# Un_C8051F340_V2_0.net
KiCad netlist of a schematic drawn in EAGLE
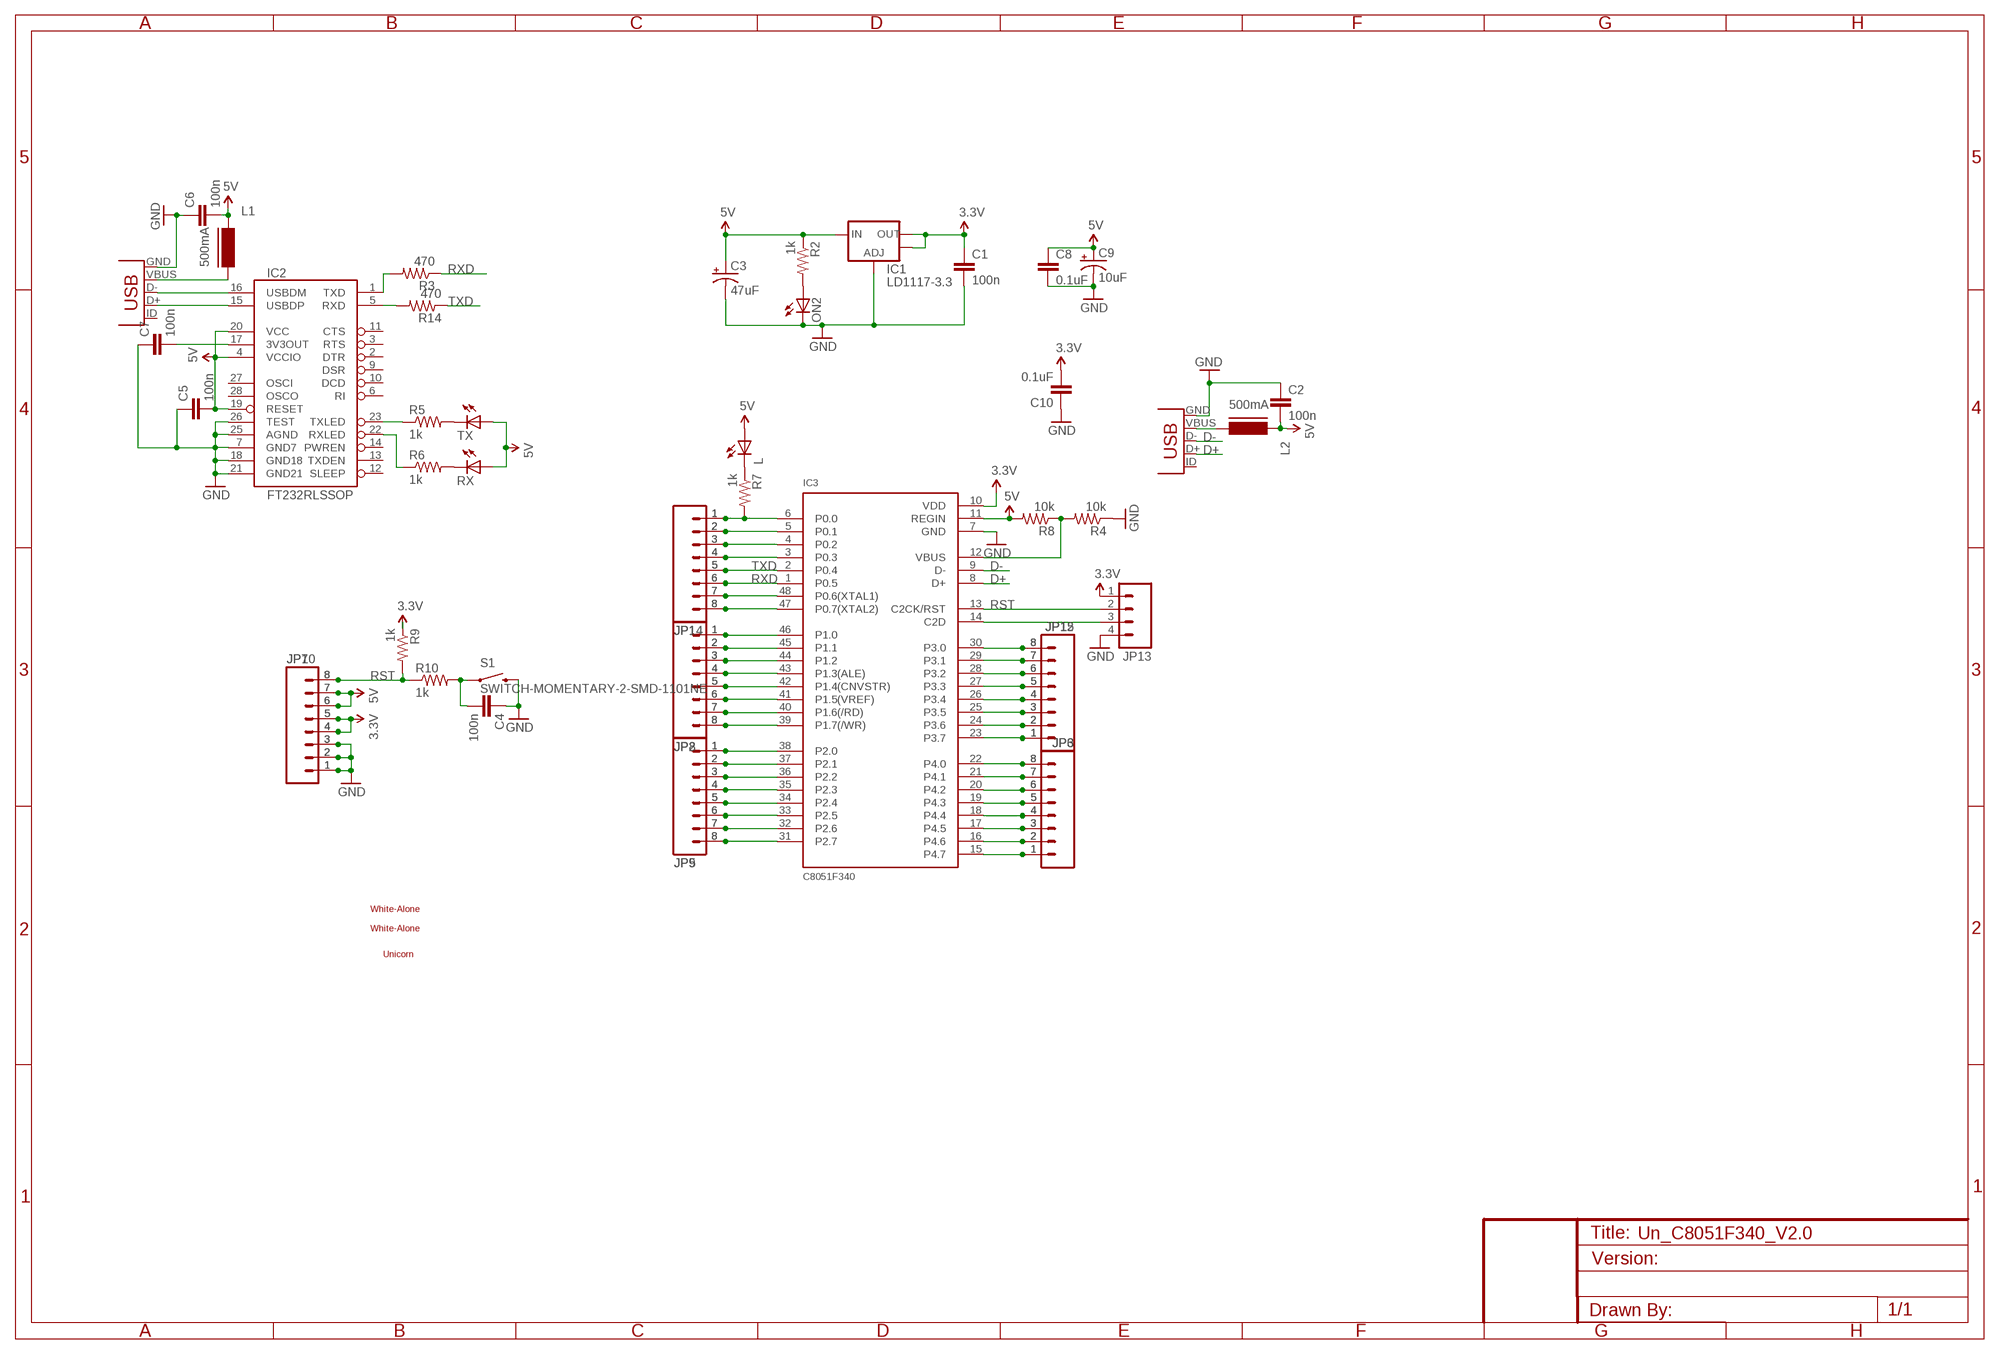
[diagram p0: schematic, sheet 1]

(export (version "E")
  (design (tool "Eeschema 10.0.6"))
  (components
    (comp (ref "C1")
      (value "100n")
      (footprint "eagle-import:0603-CAP")
      (libsource (lib "eagle-import") (part "2SparkFun_CAP0603-CAP"))
    )
    (comp (ref "C2")
      (value "100n")
      (footprint "eagle-import:0603-CAP")
      (libsource (lib "eagle-import") (part "CAP0603-CAP"))
    )
    (comp (ref "C3")
      (value "47uF")
      (footprint "eagle-import:PANASONIC_D")
      (libsource (lib "eagle-import") (part "CAP_POLD"))
    )
    (comp (ref "C4")
      (value "100n")
      (footprint "eagle-import:0603-CAP")
      (libsource (lib "eagle-import") (part "CAP0603-CAP"))
    )
    (comp (ref "C5")
      (value "100n")
      (footprint "eagle-import:0603-CAP")
      (libsource (lib "eagle-import") (part "2SparkFun_CAP0603-CAP"))
    )
    (comp (ref "C6")
      (value "100n")
      (footprint "eagle-import:0603-CAP")
      (libsource (lib "eagle-import") (part "2SparkFun_CAP0603-CAP"))
    )
    (comp (ref "C7")
      (value "100n")
      (footprint "eagle-import:0603-CAP")
      (libsource (lib "eagle-import") (part "2SparkFun_CAP0603-CAP"))
    )
    (comp (ref "C8")
      (value "0.1uF")
      (footprint "eagle-import:0603-CAP")
      (libsource (lib "eagle-import") (part "2SparkFun_CAP0603-CAP"))
    )
    (comp (ref "C9")
      (value "10uF")
      (footprint "eagle-import:EIA3216")
      (libsource (lib "eagle-import") (part "CAP_POL1206"))
    )
    (comp (ref "C10")
      (value "0.1uF")
      (footprint "eagle-import:0603-CAP")
      (libsource (lib "eagle-import") (part "2SparkFun_CAP0603-CAP"))
    )
    (comp (ref "IC1")
      (value "LD1117-3.3")
      (footprint "eagle-import:SOT223")
      (libsource (lib "eagle-import") (part "V_REG_LM1117SOT223"))
    )
    (comp (ref "IC2")
      (value "FT232RLSSOP")
      (footprint "eagle-import:SSOP28DB")
      (libsource (lib "eagle-import") (part "FT232RLSSOP"))
    )
    (comp (ref "IC3")
      (value "C8051F340")
      (footprint "eagle-import:TQFP48")
      (libsource (lib "eagle-import") (part "C8051F340"))
    )
    (comp (ref "JP1")
      (value "M08")
      (footprint "eagle-import:1X08")
      (libsource (lib "eagle-import") (part "M08"))
    )
    (comp (ref "JP2")
      (value "M08")
      (footprint "eagle-import:1X08")
      (libsource (lib "eagle-import") (part "M08"))
    )
    (comp (ref "JP3")
      (value "M08")
      (footprint "eagle-import:1X08")
      (libsource (lib "eagle-import") (part "M08"))
    )
    (comp (ref "JP5")
      (value "M08")
      (footprint "eagle-import:1X08")
      (libsource (lib "eagle-import") (part "M08"))
    )
    (comp (ref "JP6")
      (value "M08")
      (footprint "eagle-import:1X08")
      (libsource (lib "eagle-import") (part "M08"))
    )
    (comp (ref "JP7")
      (value "M08")
      (footprint "eagle-import:1X08")
      (libsource (lib "eagle-import") (part "M08"))
    )
    (comp (ref "JP8")
      (value "M08")
      (footprint "eagle-import:1X08")
      (libsource (lib "eagle-import") (part "M08"))
    )
    (comp (ref "JP9")
      (value "M08")
      (footprint "eagle-import:1X08")
      (libsource (lib "eagle-import") (part "M08"))
    )
    (comp (ref "JP10")
      (value "M08")
      (footprint "eagle-import:1X08")
      (libsource (lib "eagle-import") (part "M08"))
    )
    (comp (ref "JP12")
      (value "M08")
      (footprint "eagle-import:1X08")
      (libsource (lib "eagle-import") (part "M08"))
    )
    (comp (ref "JP13")
      (value "M04PTH")
      (footprint "eagle-import:1X04")
      (libsource (lib "eagle-import") (part "M04PTH"))
    )
    (comp (ref "JP14")
      (value "M08")
      (footprint "eagle-import:1X08")
      (libsource (lib "eagle-import") (part "M08"))
    )
    (comp (ref "JP15")
      (value "M08")
      (footprint "eagle-import:1X08")
      (libsource (lib "eagle-import") (part "M08"))
    )
    (comp (ref "L")
      (value "LED0805")
      (footprint "eagle-import:LED-0805")
      (libsource (lib "eagle-import") (part "LED0805"))
    )
    (comp (ref "L1")
      (value "500mA")
      (footprint "eagle-import:FB805")
      (libsource (lib "eagle-import") (part "FERRITE-0805"))
    )
    (comp (ref "L2")
      (value "500mA")
      (footprint "eagle-import:FB805")
      (libsource (lib "eagle-import") (part "FERRITE-0805"))
    )
    (comp (ref "ON2")
      (value "LED0805")
      (footprint "eagle-import:LED-0805")
      (libsource (lib "eagle-import") (part "LED0805"))
    )
    (comp (ref "R2")
      (value "1k")
      (footprint "eagle-import:0603-RES")
      (libsource (lib "eagle-import") (part "RESISTOR0603-RES"))
    )
    (comp (ref "R3")
      (value "470")
      (footprint "eagle-import:0603-RES")
      (libsource (lib "eagle-import") (part "RESISTOR0603-RES"))
    )
    (comp (ref "R4")
      (value "10k")
      (footprint "eagle-import:0603-RES")
      (libsource (lib "eagle-import") (part "RESISTOR0603-RES"))
    )
    (comp (ref "R5")
      (value "1k")
      (footprint "eagle-import:0603-RES")
      (libsource (lib "eagle-import") (part "RESISTOR0603-RES"))
    )
    (comp (ref "R6")
      (value "1k")
      (footprint "eagle-import:0603-RES")
      (libsource (lib "eagle-import") (part "RESISTOR0603-RES"))
    )
    (comp (ref "R7")
      (value "1k")
      (footprint "eagle-import:0603-RES")
      (libsource (lib "eagle-import") (part "RESISTOR0603-RES"))
    )
    (comp (ref "R8")
      (value "10k")
      (footprint "eagle-import:0603-RES")
      (libsource (lib "eagle-import") (part "RESISTOR0603-RES"))
    )
    (comp (ref "R9")
      (value "1k")
      (footprint "eagle-import:0603-RES")
      (libsource (lib "eagle-import") (part "RESISTOR0603-RES"))
    )
    (comp (ref "R10")
      (value "1k")
      (footprint "eagle-import:0603-RES")
      (libsource (lib "eagle-import") (part "RESISTOR0603-RES"))
    )
    (comp (ref "R14")
      (value "470")
      (footprint "eagle-import:0603-RES")
      (libsource (lib "eagle-import") (part "RESISTOR0603-RES"))
    )
    (comp (ref "RX")
      (value "LED0805")
      (footprint "eagle-import:LED-0805")
      (libsource (lib "eagle-import") (part "LED0805"))
    )
    (comp (ref "S1")
      (value "SWITCH-MOMENTARY-2-SMD-1101NE")
      (footprint "eagle-import:TACTILE-SWITCH-1101NE")
      (libsource (lib "eagle-import") (part "SWITCH-MOMENTARY-2-SMD-1101NE"))
    )
    (comp (ref "TX")
      (value "LED0805")
      (footprint "eagle-import:LED-0805")
      (libsource (lib "eagle-import") (part "LED0805"))
    )
    (comp (ref "U$3")
      (value "UNICORN_2")
      (footprint "eagle-import:UNICORN_2")
      (libsource (lib "eagle-import") (part "UNICORN_2"))
    )
    (comp (ref "U$7")
      (value "WHITE-ALONE_0")
      (footprint "eagle-import:WHITE-ALONE_0")
      (libsource (lib "eagle-import") (part "WHITE-ALONE_0"))
    )
    (comp (ref "U$11")
      (value "WHITE-ALONE_0")
      (footprint "eagle-import:WHITE-ALONE_0")
      (libsource (lib "eagle-import") (part "WHITE-ALONE_0"))
    )
    (comp (ref "X1")
      (value "USBSMD")
      (footprint "eagle-import:USB-MINIB")
      (libsource (lib "eagle-import") (part "USBSMD"))
    )
    (comp (ref "X2")
      (value "USBSMD")
      (footprint "eagle-import:USB-MINIB")
      (libsource (lib "eagle-import") (part "USBSMD"))
    )
  )
  (nets
    (net (code "1") (name "/D+") (class "Default")
      (node (ref "IC3") (pin "8") (pinfunction "D+_8") (pintype "bidirectional"))
      (node (ref "X1") (pin "D+") (pinfunction "D+_D+") (pintype "bidirectional"))
    )
    (net (code "2") (name "/D-") (class "Default")
      (node (ref "IC3") (pin "9") (pinfunction "D-_9") (pintype "bidirectional"))
      (node (ref "X1") (pin "D-") (pinfunction "D-_D-") (pintype "bidirectional"))
    )
    (net (code "3") (name "/RST") (class "Default")
      (node (ref "IC3") (pin "13") (pinfunction "C2CK/RST_13") (pintype "bidirectional"))
      (node (ref "JP10") (pin "8") (pinfunction "8_8") (pintype "passive"))
      (node (ref "JP13") (pin "2") (pinfunction "2_2") (pintype "passive"))
      (node (ref "JP7") (pin "8") (pinfunction "8_8") (pintype "passive"))
      (node (ref "R10") (pin "1") (pinfunction "1_1") (pintype "passive"))
      (node (ref "R9") (pin "2") (pinfunction "2_2") (pintype "passive"))
    )
    (net (code "4") (name "/RXD") (class "Default")
      (node (ref "IC3") (pin "1") (pinfunction "P0.5_1") (pintype "bidirectional"))
      (node (ref "JP1") (pin "6") (pinfunction "6_6") (pintype "passive"))
      (node (ref "JP14") (pin "6") (pinfunction "6_6") (pintype "passive"))
      (node (ref "R3") (pin "1") (pinfunction "1_1") (pintype "passive"))
    )
    (net (code "5") (name "/TXD") (class "Default")
      (node (ref "IC3") (pin "2") (pinfunction "P0.4_2") (pintype "bidirectional"))
      (node (ref "JP1") (pin "5") (pinfunction "5_5") (pintype "passive"))
      (node (ref "JP14") (pin "5") (pinfunction "5_5") (pintype "passive"))
      (node (ref "R14") (pin "1") (pinfunction "1_1") (pintype "passive"))
    )
    (net (code "6") (name "3.3V") (class "Default")
      (node (ref "C1") (pin "1") (pinfunction "1_1") (pintype "passive"))
      (node (ref "C10") (pin "2") (pinfunction "2_2") (pintype "passive"))
      (node (ref "IC1") (pin "2") (pinfunction "OUT_2") (pintype "output"))
      (node (ref "IC1") (pin "4") (pinfunction "OUT_4") (pintype "output"))
      (node (ref "IC3") (pin "10") (pinfunction "VDD_10") (pintype "power_in"))
      (node (ref "JP10") (pin "4") (pinfunction "4_4") (pintype "passive"))
      (node (ref "JP10") (pin "5") (pinfunction "5_5") (pintype "passive"))
      (node (ref "JP13") (pin "1") (pinfunction "1_1") (pintype "passive"))
      (node (ref "JP7") (pin "4") (pinfunction "4_4") (pintype "passive"))
      (node (ref "JP7") (pin "5") (pinfunction "5_5") (pintype "passive"))
      (node (ref "R9") (pin "1") (pinfunction "1_1") (pintype "passive"))
    )
    (net (code "7") (name "5V") (class "Default")
      (node (ref "C2") (pin "2") (pinfunction "2_2") (pintype "passive"))
      (node (ref "C3") (pin "+") (pinfunction "+_+") (pintype "passive"))
      (node (ref "C5") (pin "2") (pinfunction "2_2") (pintype "passive"))
      (node (ref "C6") (pin "2") (pinfunction "2_2") (pintype "passive"))
      (node (ref "C8") (pin "1") (pinfunction "1_1") (pintype "passive"))
      (node (ref "C9") (pin "A") (pinfunction "+_A") (pintype "passive"))
      (node (ref "IC1") (pin "3") (pinfunction "IN_3") (pintype "input"))
      (node (ref "IC2") (pin "19") (pinfunction "RESET_19") (pintype "input"))
      (node (ref "IC2") (pin "20") (pinfunction "VCC_20") (pintype "power_in"))
      (node (ref "IC2") (pin "4") (pinfunction "VCCIO_4") (pintype "power_in"))
      (node (ref "IC3") (pin "11") (pinfunction "REGIN_11") (pintype "power_in"))
      (node (ref "JP10") (pin "6") (pinfunction "6_6") (pintype "passive"))
      (node (ref "JP10") (pin "7") (pinfunction "7_7") (pintype "passive"))
      (node (ref "JP7") (pin "6") (pinfunction "6_6") (pintype "passive"))
      (node (ref "JP7") (pin "7") (pinfunction "7_7") (pintype "passive"))
      (node (ref "L") (pin "1") (pinfunction "A_1") (pintype "passive"))
      (node (ref "L1") (pin "1") (pinfunction "1_1") (pintype "passive"))
      (node (ref "L2") (pin "1") (pinfunction "1_1") (pintype "passive"))
      (node (ref "R2") (pin "1") (pinfunction "1_1") (pintype "passive"))
      (node (ref "R8") (pin "2") (pinfunction "2_2") (pintype "passive"))
      (node (ref "RX") (pin "1") (pinfunction "A_1") (pintype "passive"))
      (node (ref "TX") (pin "1") (pinfunction "A_1") (pintype "passive"))
    )
    (net (code "8") (name "GND") (class "Default")
      (node (ref "C1") (pin "2") (pinfunction "2_2") (pintype "passive"))
      (node (ref "C10") (pin "1") (pinfunction "1_1") (pintype "passive"))
      (node (ref "C2") (pin "1") (pinfunction "1_1") (pintype "passive"))
      (node (ref "C3") (pin "-") (pinfunction "-_-") (pintype "passive"))
      (node (ref "C4") (pin "1") (pinfunction "1_1") (pintype "passive"))
      (node (ref "C5") (pin "1") (pinfunction "1_1") (pintype "passive"))
      (node (ref "C6") (pin "1") (pinfunction "1_1") (pintype "passive"))
      (node (ref "C7") (pin "1") (pinfunction "1_1") (pintype "passive"))
      (node (ref "C8") (pin "2") (pinfunction "2_2") (pintype "passive"))
      (node (ref "C9") (pin "C") (pinfunction "-_C") (pintype "passive"))
      (node (ref "IC1") (pin "1") (pinfunction "ADJ_1") (pintype "input"))
      (node (ref "IC2") (pin "18") (pinfunction "GND18_18") (pintype "power_in"))
      (node (ref "IC2") (pin "21") (pinfunction "GND21_21") (pintype "power_in"))
      (node (ref "IC2") (pin "25") (pinfunction "AGND_25") (pintype "power_in"))
      (node (ref "IC2") (pin "26") (pinfunction "TEST_26") (pintype "input"))
      (node (ref "IC2") (pin "7") (pinfunction "GND7_7") (pintype "power_in"))
      (node (ref "IC3") (pin "7") (pinfunction "GND_7") (pintype "power_in"))
      (node (ref "JP10") (pin "1") (pinfunction "1_1") (pintype "passive"))
      (node (ref "JP10") (pin "2") (pinfunction "2_2") (pintype "passive"))
      (node (ref "JP10") (pin "3") (pinfunction "3_3") (pintype "passive"))
      (node (ref "JP13") (pin "4") (pinfunction "4_4") (pintype "passive"))
      (node (ref "JP7") (pin "1") (pinfunction "1_1") (pintype "passive"))
      (node (ref "JP7") (pin "2") (pinfunction "2_2") (pintype "passive"))
      (node (ref "JP7") (pin "3") (pinfunction "3_3") (pintype "passive"))
      (node (ref "ON2") (pin "2") (pinfunction "C_2") (pintype "passive"))
      (node (ref "R4") (pin "1") (pinfunction "1_1") (pintype "passive"))
      (node (ref "S1") (pin "P$2") (pinfunction "2_P$2") (pintype "passive"))
      (node (ref "X1") (pin "GND") (pinfunction "GND_GND") (pintype "bidirectional"))
      (node (ref "X2") (pin "GND") (pinfunction "GND_GND") (pintype "bidirectional"))
    )
    (net (code "9") (name "Net-(IC2-3V3OUT)") (class "Default")
      (node (ref "C7") (pin "2") (pinfunction "2_2") (pintype "passive"))
      (node (ref "IC2") (pin "17") (pinfunction "3V3OUT_17") (pintype "output"))
    )
    (net (code "10") (name "Net-(IC2-RXD)") (class "Default")
      (node (ref "IC2") (pin "5") (pinfunction "RXD_5") (pintype "input"))
      (node (ref "R14") (pin "2") (pinfunction "2_2") (pintype "passive"))
    )
    (net (code "11") (name "Net-(IC2-RXLED)") (class "Default")
      (node (ref "IC2") (pin "22") (pinfunction "RXLED_22") (pintype "input"))
      (node (ref "R6") (pin "1") (pinfunction "1_1") (pintype "passive"))
    )
    (net (code "12") (name "Net-(IC2-TXD)") (class "Default")
      (node (ref "IC2") (pin "1") (pinfunction "TXD_1") (pintype "output"))
      (node (ref "R3") (pin "2") (pinfunction "2_2") (pintype "passive"))
    )
    (net (code "13") (name "Net-(IC2-TXLED)") (class "Default")
      (node (ref "IC2") (pin "23") (pinfunction "TXLED_23") (pintype "input"))
      (node (ref "R5") (pin "1") (pinfunction "1_1") (pintype "passive"))
    )
    (net (code "14") (name "Net-(IC2-USBDM)") (class "Default")
      (node (ref "IC2") (pin "16") (pinfunction "USBDM_16") (pintype "bidirectional"))
      (node (ref "X2") (pin "D-") (pinfunction "D-_D-") (pintype "bidirectional"))
    )
    (net (code "15") (name "Net-(IC2-USBDP)") (class "Default")
      (node (ref "IC2") (pin "15") (pinfunction "USBDP_15") (pintype "bidirectional"))
      (node (ref "X2") (pin "D+") (pinfunction "D+_D+") (pintype "bidirectional"))
    )
    (net (code "16") (name "Net-(IC3-C2D)") (class "Default")
      (node (ref "IC3") (pin "14") (pinfunction "C2D_14") (pintype "bidirectional"))
      (node (ref "JP13") (pin "3") (pinfunction "3_3") (pintype "passive"))
    )
    (net (code "17") (name "Net-(IC3-P0.0)") (class "Default")
      (node (ref "IC3") (pin "6") (pinfunction "P0.0_6") (pintype "bidirectional"))
      (node (ref "JP1") (pin "1") (pinfunction "1_1") (pintype "passive"))
      (node (ref "JP14") (pin "1") (pinfunction "1_1") (pintype "passive"))
      (node (ref "R7") (pin "2") (pinfunction "2_2") (pintype "passive"))
    )
    (net (code "18") (name "Net-(IC3-P0.1)") (class "Default")
      (node (ref "IC3") (pin "5") (pinfunction "P0.1_5") (pintype "bidirectional"))
      (node (ref "JP1") (pin "2") (pinfunction "2_2") (pintype "passive"))
      (node (ref "JP14") (pin "2") (pinfunction "2_2") (pintype "passive"))
    )
    (net (code "19") (name "Net-(IC3-P0.2)") (class "Default")
      (node (ref "IC3") (pin "4") (pinfunction "P0.2_4") (pintype "bidirectional"))
      (node (ref "JP1") (pin "3") (pinfunction "3_3") (pintype "passive"))
      (node (ref "JP14") (pin "3") (pinfunction "3_3") (pintype "passive"))
    )
    (net (code "20") (name "Net-(IC3-P0.3)") (class "Default")
      (node (ref "IC3") (pin "3") (pinfunction "P0.3_3") (pintype "bidirectional"))
      (node (ref "JP1") (pin "4") (pinfunction "4_4") (pintype "passive"))
      (node (ref "JP14") (pin "4") (pinfunction "4_4") (pintype "passive"))
    )
    (net (code "21") (name "Net-(IC3-P0.6(XTAL1))") (class "Default")
      (node (ref "IC3") (pin "48") (pinfunction "P0.6(XTAL1)_48") (pintype "bidirectional"))
      (node (ref "JP1") (pin "7") (pinfunction "7_7") (pintype "passive"))
      (node (ref "JP14") (pin "7") (pinfunction "7_7") (pintype "passive"))
    )
    (net (code "22") (name "Net-(IC3-P0.7(XTAL2))") (class "Default")
      (node (ref "IC3") (pin "47") (pinfunction "P0.7(XTAL2)_47") (pintype "bidirectional"))
      (node (ref "JP1") (pin "8") (pinfunction "8_8") (pintype "passive"))
      (node (ref "JP14") (pin "8") (pinfunction "8_8") (pintype "passive"))
    )
    (net (code "23") (name "Net-(IC3-P1.0)") (class "Default")
      (node (ref "IC3") (pin "46") (pinfunction "P1.0_46") (pintype "bidirectional"))
      (node (ref "JP2") (pin "1") (pinfunction "1_1") (pintype "passive"))
      (node (ref "JP8") (pin "1") (pinfunction "1_1") (pintype "passive"))
    )
    (net (code "24") (name "Net-(IC3-P1.1)") (class "Default")
      (node (ref "IC3") (pin "45") (pinfunction "P1.1_45") (pintype "bidirectional"))
      (node (ref "JP2") (pin "2") (pinfunction "2_2") (pintype "passive"))
      (node (ref "JP8") (pin "2") (pinfunction "2_2") (pintype "passive"))
    )
    (net (code "25") (name "Net-(IC3-P1.2)") (class "Default")
      (node (ref "IC3") (pin "44") (pinfunction "P1.2_44") (pintype "bidirectional"))
      (node (ref "JP2") (pin "3") (pinfunction "3_3") (pintype "passive"))
      (node (ref "JP8") (pin "3") (pinfunction "3_3") (pintype "passive"))
    )
    (net (code "26") (name "Net-(IC3-P1.3(ALE))") (class "Default")
      (node (ref "IC3") (pin "43") (pinfunction "P1.3(ALE)_43") (pintype "bidirectional"))
      (node (ref "JP2") (pin "4") (pinfunction "4_4") (pintype "passive"))
      (node (ref "JP8") (pin "4") (pinfunction "4_4") (pintype "passive"))
    )
    (net (code "27") (name "Net-(IC3-P1.4(CNVSTR))") (class "Default")
      (node (ref "IC3") (pin "42") (pinfunction "P1.4(CNVSTR)_42") (pintype "bidirectional"))
      (node (ref "JP2") (pin "5") (pinfunction "5_5") (pintype "passive"))
      (node (ref "JP8") (pin "5") (pinfunction "5_5") (pintype "passive"))
    )
    (net (code "28") (name "Net-(IC3-P1.5(VREF))") (class "Default")
      (node (ref "IC3") (pin "41") (pinfunction "P1.5(VREF)_41") (pintype "bidirectional"))
      (node (ref "JP2") (pin "6") (pinfunction "6_6") (pintype "passive"))
      (node (ref "JP8") (pin "6") (pinfunction "6_6") (pintype "passive"))
    )
    (net (code "29") (name "Net-(IC3-P1.6({slash}RD))") (class "Default")
      (node (ref "IC3") (pin "40") (pinfunction "P1.6(/RD)_40") (pintype "bidirectional"))
      (node (ref "JP2") (pin "7") (pinfunction "7_7") (pintype "passive"))
      (node (ref "JP8") (pin "7") (pinfunction "7_7") (pintype "passive"))
    )
    (net (code "30") (name "Net-(IC3-P1.7({slash}WR))") (class "Default")
      (node (ref "IC3") (pin "39") (pinfunction "P1.7(/WR)_39") (pintype "bidirectional"))
      (node (ref "JP2") (pin "8") (pinfunction "8_8") (pintype "passive"))
      (node (ref "JP8") (pin "8") (pinfunction "8_8") (pintype "passive"))
    )
    (net (code "31") (name "Net-(IC3-P2.0)") (class "Default")
      (node (ref "IC3") (pin "38") (pinfunction "P2.0_38") (pintype "bidirectional"))
      (node (ref "JP5") (pin "1") (pinfunction "1_1") (pintype "passive"))
      (node (ref "JP9") (pin "1") (pinfunction "1_1") (pintype "passive"))
    )
    (net (code "32") (name "Net-(IC3-P2.1)") (class "Default")
      (node (ref "IC3") (pin "37") (pinfunction "P2.1_37") (pintype "bidirectional"))
      (node (ref "JP5") (pin "2") (pinfunction "2_2") (pintype "passive"))
      (node (ref "JP9") (pin "2") (pinfunction "2_2") (pintype "passive"))
    )
    (net (code "33") (name "Net-(IC3-P2.2)") (class "Default")
      (node (ref "IC3") (pin "36") (pinfunction "P2.2_36") (pintype "bidirectional"))
      (node (ref "JP5") (pin "3") (pinfunction "3_3") (pintype "passive"))
      (node (ref "JP9") (pin "3") (pinfunction "3_3") (pintype "passive"))
    )
    (net (code "34") (name "Net-(IC3-P2.3)") (class "Default")
      (node (ref "IC3") (pin "35") (pinfunction "P2.3_35") (pintype "bidirectional"))
      (node (ref "JP5") (pin "4") (pinfunction "4_4") (pintype "passive"))
      (node (ref "JP9") (pin "4") (pinfunction "4_4") (pintype "passive"))
    )
    (net (code "35") (name "Net-(IC3-P2.4)") (class "Default")
      (node (ref "IC3") (pin "34") (pinfunction "P2.4_34") (pintype "bidirectional"))
      (node (ref "JP5") (pin "5") (pinfunction "5_5") (pintype "passive"))
      (node (ref "JP9") (pin "5") (pinfunction "5_5") (pintype "passive"))
    )
    (net (code "36") (name "Net-(IC3-P2.5)") (class "Default")
      (node (ref "IC3") (pin "33") (pinfunction "P2.5_33") (pintype "bidirectional"))
      (node (ref "JP5") (pin "6") (pinfunction "6_6") (pintype "passive"))
      (node (ref "JP9") (pin "6") (pinfunction "6_6") (pintype "passive"))
    )
    (net (code "37") (name "Net-(IC3-P2.6)") (class "Default")
      (node (ref "IC3") (pin "32") (pinfunction "P2.6_32") (pintype "bidirectional"))
      (node (ref "JP5") (pin "7") (pinfunction "7_7") (pintype "passive"))
      (node (ref "JP9") (pin "7") (pinfunction "7_7") (pintype "passive"))
    )
    (net (code "38") (name "Net-(IC3-P2.7)") (class "Default")
      (node (ref "IC3") (pin "31") (pinfunction "P2.7_31") (pintype "bidirectional"))
      (node (ref "JP5") (pin "8") (pinfunction "8_8") (pintype "passive"))
      (node (ref "JP9") (pin "8") (pinfunction "8_8") (pintype "passive"))
    )
    (net (code "39") (name "Net-(IC3-P3.0)") (class "Default")
      (node (ref "IC3") (pin "30") (pinfunction "P3.0_30") (pintype "bidirectional"))
      (node (ref "JP12") (pin "8") (pinfunction "8_8") (pintype "passive"))
      (node (ref "JP15") (pin "8") (pinfunction "8_8") (pintype "passive"))
    )
    (net (code "40") (name "Net-(IC3-P3.1)") (class "Default")
      (node (ref "IC3") (pin "29") (pinfunction "P3.1_29") (pintype "bidirectional"))
      (node (ref "JP12") (pin "7") (pinfunction "7_7") (pintype "passive"))
      (node (ref "JP15") (pin "7") (pinfunction "7_7") (pintype "passive"))
    )
    (net (code "41") (name "Net-(IC3-P3.2)") (class "Default")
      (node (ref "IC3") (pin "28") (pinfunction "P3.2_28") (pintype "bidirectional"))
      (node (ref "JP12") (pin "6") (pinfunction "6_6") (pintype "passive"))
      (node (ref "JP15") (pin "6") (pinfunction "6_6") (pintype "passive"))
    )
    (net (code "42") (name "Net-(IC3-P3.3)") (class "Default")
      (node (ref "IC3") (pin "27") (pinfunction "P3.3_27") (pintype "bidirectional"))
      (node (ref "JP12") (pin "5") (pinfunction "5_5") (pintype "passive"))
      (node (ref "JP15") (pin "5") (pinfunction "5_5") (pintype "passive"))
    )
    (net (code "43") (name "Net-(IC3-P3.4)") (class "Default")
      (node (ref "IC3") (pin "26") (pinfunction "P3.4_26") (pintype "bidirectional"))
      (node (ref "JP12") (pin "4") (pinfunction "4_4") (pintype "passive"))
      (node (ref "JP15") (pin "4") (pinfunction "4_4") (pintype "passive"))
    )
    (net (code "44") (name "Net-(IC3-P3.5)") (class "Default")
      (node (ref "IC3") (pin "25") (pinfunction "P3.5_25") (pintype "bidirectional"))
      (node (ref "JP12") (pin "3") (pinfunction "3_3") (pintype "passive"))
      (node (ref "JP15") (pin "3") (pinfunction "3_3") (pintype "passive"))
    )
    (net (code "45") (name "Net-(IC3-P3.6)") (class "Default")
      (node (ref "IC3") (pin "24") (pinfunction "P3.6_24") (pintype "bidirectional"))
      (node (ref "JP12") (pin "2") (pinfunction "2_2") (pintype "passive"))
      (node (ref "JP15") (pin "2") (pinfunction "2_2") (pintype "passive"))
    )
    (net (code "46") (name "Net-(IC3-P3.7)") (class "Default")
      (node (ref "IC3") (pin "23") (pinfunction "P3.7_23") (pintype "bidirectional"))
      (node (ref "JP12") (pin "1") (pinfunction "1_1") (pintype "passive"))
      (node (ref "JP15") (pin "1") (pinfunction "1_1") (pintype "passive"))
    )
    (net (code "47") (name "Net-(IC3-P4.0)") (class "Default")
      (node (ref "IC3") (pin "22") (pinfunction "P4.0_22") (pintype "bidirectional"))
      (node (ref "JP3") (pin "8") (pinfunction "8_8") (pintype "passive"))
      (node (ref "JP6") (pin "8") (pinfunction "8_8") (pintype "passive"))
    )
    (net (code "48") (name "Net-(IC3-P4.1)") (class "Default")
      (node (ref "IC3") (pin "21") (pinfunction "P4.1_21") (pintype "bidirectional"))
      (node (ref "JP3") (pin "7") (pinfunction "7_7") (pintype "passive"))
      (node (ref "JP6") (pin "7") (pinfunction "7_7") (pintype "passive"))
    )
    (net (code "49") (name "Net-(IC3-P4.2)") (class "Default")
      (node (ref "IC3") (pin "20") (pinfunction "P4.2_20") (pintype "bidirectional"))
      (node (ref "JP3") (pin "6") (pinfunction "6_6") (pintype "passive"))
      (node (ref "JP6") (pin "6") (pinfunction "6_6") (pintype "passive"))
    )
    (net (code "50") (name "Net-(IC3-P4.3)") (class "Default")
      (node (ref "IC3") (pin "19") (pinfunction "P4.3_19") (pintype "bidirectional"))
      (node (ref "JP3") (pin "5") (pinfunction "5_5") (pintype "passive"))
      (node (ref "JP6") (pin "5") (pinfunction "5_5") (pintype "passive"))
    )
    (net (code "51") (name "Net-(IC3-P4.4)") (class "Default")
      (node (ref "IC3") (pin "18") (pinfunction "P4.4_18") (pintype "bidirectional"))
      (node (ref "JP3") (pin "4") (pinfunction "4_4") (pintype "passive"))
      (node (ref "JP6") (pin "4") (pinfunction "4_4") (pintype "passive"))
    )
    (net (code "52") (name "Net-(IC3-P4.5)") (class "Default")
      (node (ref "IC3") (pin "17") (pinfunction "P4.5_17") (pintype "bidirectional"))
      (node (ref "JP3") (pin "3") (pinfunction "3_3") (pintype "passive"))
      (node (ref "JP6") (pin "3") (pinfunction "3_3") (pintype "passive"))
    )
    (net (code "53") (name "Net-(IC3-P4.6)") (class "Default")
      (node (ref "IC3") (pin "16") (pinfunction "P4.6_16") (pintype "bidirectional"))
      (node (ref "JP3") (pin "2") (pinfunction "2_2") (pintype "passive"))
      (node (ref "JP6") (pin "2") (pinfunction "2_2") (pintype "passive"))
    )
    (net (code "54") (name "Net-(IC3-P4.7)") (class "Default")
      (node (ref "IC3") (pin "15") (pinfunction "P4.7_15") (pintype "bidirectional"))
      (node (ref "JP3") (pin "1") (pinfunction "1_1") (pintype "passive"))
      (node (ref "JP6") (pin "1") (pinfunction "1_1") (pintype "passive"))
    )
    (net (code "55") (name "Net-(IC3-VBUS)") (class "Default")
      (node (ref "IC3") (pin "12") (pinfunction "VBUS_12") (pintype "power_in"))
      (node (ref "R4") (pin "2") (pinfunction "2_2") (pintype "passive"))
      (node (ref "R8") (pin "1") (pinfunction "1_1") (pintype "passive"))
    )
    (net (code "56") (name "Net-(L-C)") (class "Default")
      (node (ref "L") (pin "2") (pinfunction "C_2") (pintype "passive"))
      (node (ref "R7") (pin "1") (pinfunction "1_1") (pintype "passive"))
    )
    (net (code "57") (name "Net-(L1-Pad2)") (class "Default")
      (node (ref "L1") (pin "2") (pinfunction "2_2") (pintype "passive"))
      (node (ref "X2") (pin "VBUS") (pinfunction "VBUS_VBUS") (pintype "bidirectional"))
    )
    (net (code "58") (name "Net-(L2-Pad2)") (class "Default")
      (node (ref "L2") (pin "2") (pinfunction "2_2") (pintype "passive"))
      (node (ref "X1") (pin "VBUS") (pinfunction "VBUS_VBUS") (pintype "bidirectional"))
    )
    (net (code "59") (name "Net-(ON2-A)") (class "Default")
      (node (ref "ON2") (pin "1") (pinfunction "A_1") (pintype "passive"))
      (node (ref "R2") (pin "2") (pinfunction "2_2") (pintype "passive"))
    )
    (net (code "60") (name "Net-(RX-C)") (class "Default")
      (node (ref "R6") (pin "2") (pinfunction "2_2") (pintype "passive"))
      (node (ref "RX") (pin "2") (pinfunction "C_2") (pintype "passive"))
    )
    (net (code "61") (name "Net-(S1-1)") (class "Default")
      (node (ref "C4") (pin "2") (pinfunction "2_2") (pintype "passive"))
      (node (ref "R10") (pin "2") (pinfunction "2_2") (pintype "passive"))
      (node (ref "S1") (pin "P$1") (pinfunction "1_P$1") (pintype "passive"))
    )
    (net (code "62") (name "Net-(TX-C)") (class "Default")
      (node (ref "R5") (pin "2") (pinfunction "2_2") (pintype "passive"))
      (node (ref "TX") (pin "2") (pinfunction "C_2") (pintype "passive"))
    )
    (net (code "63") (name "unconnected-(IC2-CTS-Pad11)") (class "Default")
      (node (ref "IC2") (pin "11") (pinfunction "CTS_11") (pintype "input"))
    )
    (net (code "64") (name "unconnected-(IC2-DCD-Pad10)") (class "Default")
      (node (ref "IC2") (pin "10") (pinfunction "DCD_10") (pintype "input"))
    )
    (net (code "65") (name "unconnected-(IC2-DSR-Pad9)") (class "Default")
      (node (ref "IC2") (pin "9") (pinfunction "DSR_9") (pintype "input"))
    )
    (net (code "66") (name "unconnected-(IC2-DTR-Pad2)") (class "Default")
      (node (ref "IC2") (pin "2") (pinfunction "DTR_2") (pintype "output"))
    )
    (net (code "67") (name "unconnected-(IC2-OSCI-Pad27)") (class "Default")
      (node (ref "IC2") (pin "27") (pinfunction "OSCI_27") (pintype "input"))
    )
    (net (code "68") (name "unconnected-(IC2-OSCO-Pad28)") (class "Default")
      (node (ref "IC2") (pin "28") (pinfunction "OSCO_28") (pintype "output"))
    )
    (net (code "69") (name "unconnected-(IC2-PWREN-Pad14)") (class "Default")
      (node (ref "IC2") (pin "14") (pinfunction "PWREN_14") (pintype "input"))
    )
    (net (code "70") (name "unconnected-(IC2-RI-Pad6)") (class "Default")
      (node (ref "IC2") (pin "6") (pinfunction "RI_6") (pintype "input"))
    )
    (net (code "71") (name "unconnected-(IC2-RTS-Pad3)") (class "Default")
      (node (ref "IC2") (pin "3") (pinfunction "RTS_3") (pintype "output"))
    )
    (net (code "72") (name "unconnected-(IC2-SLEEP-Pad12)") (class "Default")
      (node (ref "IC2") (pin "12") (pinfunction "SLEEP_12") (pintype "input"))
    )
    (net (code "73") (name "unconnected-(IC2-TXDEN-Pad13)") (class "Default")
      (node (ref "IC2") (pin "13") (pinfunction "TXDEN_13") (pintype "input"))
    )
    (net (code "74") (name "unconnected-(X1-USBID-PadID)") (class "Default")
      (node (ref "X1") (pin "ID") (pinfunction "USBID_ID") (pintype "bidirectional"))
    )
    (net (code "75") (name "unconnected-(X2-USBID-PadID)") (class "Default")
      (node (ref "X2") (pin "ID") (pinfunction "USBID_ID") (pintype "bidirectional"))
    )
  )
)
